# Power_Supply.net
KiCad netlist of a schematic drawn in Altium Designer
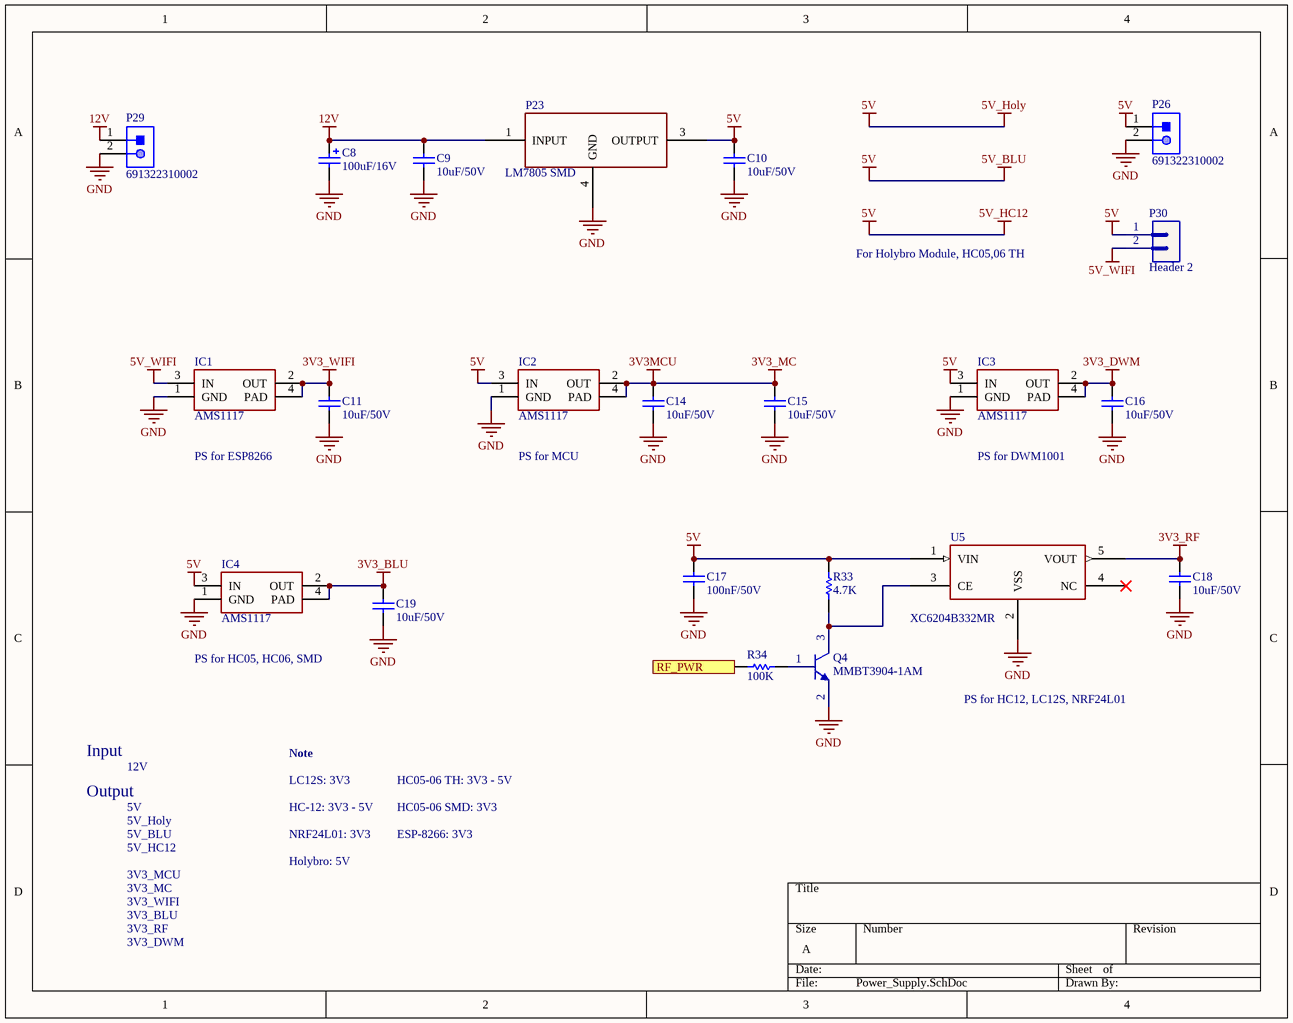
[diagram p0: Power_Supply.SchDoc]

(export (version "E")
  (design (tool "Eeschema 10.0.6"))
  (components
    (comp (ref "C8")
      (value "100uF/16V")
      (footprint "Capacitor:CAP-SM-AL-SIZE-D-D6L6")
      (description "CAP ALUM 100UF 20% 16V SMD")
      (fields
        (field (name "MANUFACTURER") "Nichicon")
        (field (name "MANUFACTURER PART NUMBER") "UWX1C101MCL1GB")
      )
      (libsource (lib "Capacitor") (part "Cap-Al-100uF-16V-D6L5"))
    )
    (comp (ref "C9")
      (value "10uF/50V")
      (footprint "CAP-SM-0805")
      (description "CAP CER 10UF 50V X5R 0805")
      (fields
        (field (name "MANUFACTURER") "Yageo")
        (field (name "MANUFACTURER PART NUMBER") "CC0805KKX5R9BB106")
      )
      (libsource (lib "Capacitor") (part "Cap-10uF-50V-0805"))
    )
    (comp (ref "C10")
      (value "10uF/50V")
      (footprint "CAP-SM-0805")
      (description "CAP CER 10UF 50V X5R 0805")
      (fields
        (field (name "MANUFACTURER") "Yageo")
        (field (name "MANUFACTURER PART NUMBER") "CC0805KKX5R9BB106")
      )
      (libsource (lib "Capacitor") (part "Cap-10uF-50V-0805"))
    )
    (comp (ref "C11")
      (value "10uF/50V")
      (footprint "CAP-SM-0805")
      (description "CAP CER 10UF 50V X5R 0805")
      (fields
        (field (name "MANUFACTURER") "Yageo")
        (field (name "MANUFACTURER PART NUMBER") "CC0805KKX5R9BB106")
      )
      (libsource (lib "Capacitor") (part "Cap-10uF-50V-0805"))
    )
    (comp (ref "C14")
      (value "10uF/50V")
      (footprint "CAP-SM-0805")
      (description "CAP CER 10UF 50V X5R 0805")
      (fields
        (field (name "MANUFACTURER") "Yageo")
        (field (name "MANUFACTURER PART NUMBER") "CC0805KKX5R9BB106")
      )
      (libsource (lib "Capacitor") (part "Cap-10uF-50V-0805"))
    )
    (comp (ref "C15")
      (value "10uF/50V")
      (footprint "CAP-SM-0805")
      (description "CAP CER 10UF 50V X5R 0805")
      (fields
        (field (name "MANUFACTURER") "Yageo")
        (field (name "MANUFACTURER PART NUMBER") "CC0805KKX5R9BB106")
      )
      (libsource (lib "Capacitor") (part "Cap-10uF-50V-0805"))
    )
    (comp (ref "C16")
      (value "10uF/50V")
      (footprint "CAP-SM-0805")
      (description "CAP CER 10UF 50V X5R 0805")
      (fields
        (field (name "MANUFACTURER") "Yageo")
        (field (name "MANUFACTURER PART NUMBER") "CC0805KKX5R9BB106")
      )
      (libsource (lib "Capacitor") (part "Cap-10uF-50V-0805"))
    )
    (comp (ref "C17")
      (value "100nF/50V")
      (footprint "CAP-SM-0805")
      (description "CAP CER 0.1UF 50V Y5V 0805")
      (fields
        (field (name "MANUFACTURER") "Samsung Electro-Mechanics")
        (field (name "MANUFACTURER PART NUMBER") "CL21F104ZBCNNNC")
      )
      (libsource (lib "Capacitor") (part "Cap-100nF-50V-0805"))
    )
    (comp (ref "C18")
      (value "10uF/50V")
      (footprint "CAP-SM-0805")
      (description "CAP CER 10UF 50V X5R 0805")
      (fields
        (field (name "MANUFACTURER") "Yageo")
        (field (name "MANUFACTURER PART NUMBER") "CC0805KKX5R9BB106")
      )
      (libsource (lib "Capacitor") (part "Cap-10uF-50V-0805"))
    )
    (comp (ref "C19")
      (value "10uF/50V")
      (footprint "CAP-SM-0805")
      (description "CAP CER 10UF 50V X5R 0805")
      (fields
        (field (name "MANUFACTURER") "Yageo")
        (field (name "MANUFACTURER PART NUMBER") "CC0805KKX5R9BB106")
      )
      (libsource (lib "Capacitor") (part "Cap-10uF-50V-0805"))
    )
    (comp (ref "IC1")
      (value "AMS1117")
      (footprint "PI:SOT223")
      (description "Available in 1.8V, 2.5V, 2.85V, 3.3V, 5V, and  Adjustable Versions")
      (libsource (lib "PI") (part "AMS1117"))
    )
    (comp (ref "IC2")
      (value "AMS1117")
      (footprint "PI:SOT223")
      (description "Available in 1.8V, 2.5V, 2.85V, 3.3V, 5V, and  Adjustable Versions")
      (libsource (lib "PI") (part "AMS1117"))
    )
    (comp (ref "IC3")
      (value "AMS1117")
      (footprint "PI:SOT223")
      (description "Available in 1.8V, 2.5V, 2.85V, 3.3V, 5V, and  Adjustable Versions")
      (libsource (lib "PI") (part "AMS1117"))
    )
    (comp (ref "IC4")
      (value "AMS1117")
      (footprint "PI:SOT223")
      (description "Available in 1.8V, 2.5V, 2.85V, 3.3V, 5V, and  Adjustable Versions")
      (libsource (lib "PI") (part "AMS1117"))
    )
    (comp (ref "P23")
      (value "LM7805 SMD")
      (footprint "D2PAK_STM")
      (libsource (lib "PIF_robot") (part "LM7805 SMD"))
    )
    (comp (ref "P26")
      (value "691322310002")
      (footprint "691322310002")
      (description "WR-TBL Serie 322 Horizontal PCB Header, Pluggable, pitch 3.81mm, 2p")
      (fields (field (name "PUBLISHER") "Wurth Elektronik"))
      (libsource (lib "691322310002_Altium_WR-TBL_rev19a") (part "691322310002"))
    )
    (comp (ref "P29")
      (value "691322310002")
      (footprint "691322310002")
      (description "WR-TBL Serie 322 Horizontal PCB Header, Pluggable, pitch 3.81mm, 2p")
      (fields (field (name "PUBLISHER") "Wurth Elektronik"))
      (libsource (lib "691322310002_Altium_WR-TBL_rev19a") (part "691322310002"))
    )
    (comp (ref "P30")
      (value "Header 2")
      (footprint "JP2")
      (description "Header, 2-Pin")
      (fields (field (name "PUBLISHER") "Altium Limited"))
      (libsource (lib "PIF_C16_lib") (part "Header 2"))
    )
    (comp (ref "Q4")
      (value "MMBT3904-1AM")
      (footprint "BJT:SOT23_NEX")
      (libsource (lib "BJT") (part "MMBT3904-1AM"))
    )
    (comp (ref "R33")
      (value "4.7K")
      (footprint "Resistor:RES-SM-0805")
      (description "RES SMD 4.7K OHM 5% 1/8W 0805")
      (fields
        (field (name "MANUFACTURER") "Yageo")
        (field (name "MANUFACTURER PART NUMBER") "RC0805JR-074K7L")
      )
      (libsource (lib "Resistor") (part "Res-4.7K-0805"))
    )
    (comp (ref "R34")
      (value "100K")
      (footprint "Resistor:RES-SM-0805")
      (description "RES 0 OHM JUMPER 0805")
      (fields
        (field (name "MANUFACTURER") "Vishay Dale")
        (field (name "MANUFACTURER PART NUMBER") "WSL080500000ZEA9")
      )
      (libsource (lib "Resistor") (part "Res-100K-0805"))
    )
    (comp (ref "U5")
      (value "XC6204B332MR")
      (footprint "PI:XC6204/05_SOT-00")
      (fields (field (name "COPYRIGHT") "Copyright (C) 2018 Accelerated Designs. All rights reserved"))
      (libsource (lib "PI") (part "XC6204B332MR"))
    )
  )
  (nets
    (net (code "1") (name "/RF_PWR") (class "Default")
      (node (ref "R34") (pin "1") (pinfunction "1_1") (pintype "passive"))
    )
    (net (code "2") (name "3V3MCU") (class "Default")
      (node (ref "C14") (pin "2") (pinfunction "2_2") (pintype "passive"))
      (node (ref "C15") (pin "2") (pinfunction "2_2") (pintype "passive"))
      (node (ref "IC2") (pin "2") (pinfunction "OUT_2") (pintype "passive"))
      (node (ref "IC2") (pin "4") (pinfunction "PAD_4") (pintype "passive"))
    )
    (net (code "3") (name "3V3_BLU") (class "Default")
      (node (ref "C19") (pin "2") (pinfunction "2_2") (pintype "passive"))
      (node (ref "IC4") (pin "2") (pinfunction "OUT_2") (pintype "passive"))
      (node (ref "IC4") (pin "4") (pinfunction "PAD_4") (pintype "passive"))
    )
    (net (code "4") (name "3V3_DWM") (class "Default")
      (node (ref "C16") (pin "2") (pinfunction "2_2") (pintype "passive"))
      (node (ref "IC3") (pin "2") (pinfunction "OUT_2") (pintype "passive"))
      (node (ref "IC3") (pin "4") (pinfunction "PAD_4") (pintype "passive"))
    )
    (net (code "5") (name "3V3_RF") (class "Default")
      (node (ref "C18") (pin "2") (pinfunction "2_2") (pintype "passive"))
      (node (ref "U5") (pin "5") (pinfunction "VOUT_5") (pintype "output"))
    )
    (net (code "6") (name "3V3_WIFI") (class "Default")
      (node (ref "C11") (pin "2") (pinfunction "2_2") (pintype "passive"))
      (node (ref "IC1") (pin "2") (pinfunction "OUT_2") (pintype "passive"))
      (node (ref "IC1") (pin "4") (pinfunction "PAD_4") (pintype "passive"))
    )
    (net (code "7") (name "5V") (class "Default")
      (node (ref "C10") (pin "2") (pinfunction "2_2") (pintype "passive"))
      (node (ref "C17") (pin "2") (pinfunction "2_2") (pintype "passive"))
      (node (ref "IC2") (pin "3") (pinfunction "IN_3") (pintype "passive"))
      (node (ref "IC3") (pin "3") (pinfunction "IN_3") (pintype "passive"))
      (node (ref "IC4") (pin "3") (pinfunction "IN_3") (pintype "passive"))
      (node (ref "P23") (pin "3") (pinfunction "OUTPUT_3") (pintype "passive"))
      (node (ref "P26") (pin "1") (pinfunction "1_1") (pintype "passive"))
      (node (ref "P30") (pin "1") (pinfunction "1_1") (pintype "passive"))
      (node (ref "R33") (pin "2") (pinfunction "2_2") (pintype "passive"))
      (node (ref "U5") (pin "1") (pinfunction "VIN_1") (pintype "input"))
    )
    (net (code "8") (name "5V_WIFI") (class "Default")
      (node (ref "IC1") (pin "3") (pinfunction "IN_3") (pintype "passive"))
      (node (ref "P30") (pin "2") (pinfunction "2_2") (pintype "passive"))
    )
    (net (code "9") (name "12V") (class "Default")
      (node (ref "C8") (pin "1") (pinfunction "1_1") (pintype "passive"))
      (node (ref "C9") (pin "1") (pinfunction "1_1") (pintype "passive"))
      (node (ref "P23") (pin "1") (pinfunction "INPUT_1") (pintype "passive"))
      (node (ref "P29") (pin "1") (pinfunction "1_1") (pintype "passive"))
    )
    (net (code "10") (name "GND") (class "Default")
      (node (ref "C10") (pin "1") (pinfunction "1_1") (pintype "passive"))
      (node (ref "C11") (pin "1") (pinfunction "1_1") (pintype "passive"))
      (node (ref "C14") (pin "1") (pinfunction "1_1") (pintype "passive"))
      (node (ref "C15") (pin "1") (pinfunction "1_1") (pintype "passive"))
      (node (ref "C16") (pin "1") (pinfunction "1_1") (pintype "passive"))
      (node (ref "C17") (pin "1") (pinfunction "1_1") (pintype "passive"))
      (node (ref "C18") (pin "1") (pinfunction "1_1") (pintype "passive"))
      (node (ref "C19") (pin "1") (pinfunction "1_1") (pintype "passive"))
      (node (ref "C8") (pin "2") (pinfunction "2_2") (pintype "passive"))
      (node (ref "C9") (pin "2") (pinfunction "2_2") (pintype "passive"))
      (node (ref "IC1") (pin "1") (pinfunction "GND_1") (pintype "passive"))
      (node (ref "IC2") (pin "1") (pinfunction "GND_1") (pintype "passive"))
      (node (ref "IC3") (pin "1") (pinfunction "GND_1") (pintype "passive"))
      (node (ref "IC4") (pin "1") (pinfunction "GND_1") (pintype "passive"))
      (node (ref "P23") (pin "4") (pinfunction "GND_4") (pintype "passive"))
      (node (ref "P26") (pin "2") (pinfunction "2_2") (pintype "passive"))
      (node (ref "P29") (pin "2") (pinfunction "2_2") (pintype "passive"))
      (node (ref "Q4") (pin "2") (pinfunction "E_2") (pintype "passive"))
      (node (ref "U5") (pin "2") (pinfunction "VSS_2") (pintype "passive"))
    )
    (net (code "11") (name "Net-(Q4-B)") (class "Default")
      (node (ref "Q4") (pin "1") (pinfunction "B_1") (pintype "passive"))
      (node (ref "R34") (pin "2") (pinfunction "2_2") (pintype "passive"))
    )
    (net (code "12") (name "Net-(Q4-C)") (class "Default")
      (node (ref "Q4") (pin "3") (pinfunction "C_3") (pintype "passive"))
      (node (ref "R33") (pin "1") (pinfunction "1_1") (pintype "passive"))
      (node (ref "U5") (pin "3") (pinfunction "CE_3") (pintype "passive"))
    )
    (net (code "13") (name "unconnected-(U5-NC-Pad4)") (class "Default")
      (node (ref "U5") (pin "4") (pinfunction "NC_4") (pintype "passive+no_connect"))
    )
  )
)
